# HDMI_DP.net
KiCad netlist of a schematic drawn in Altium Designer
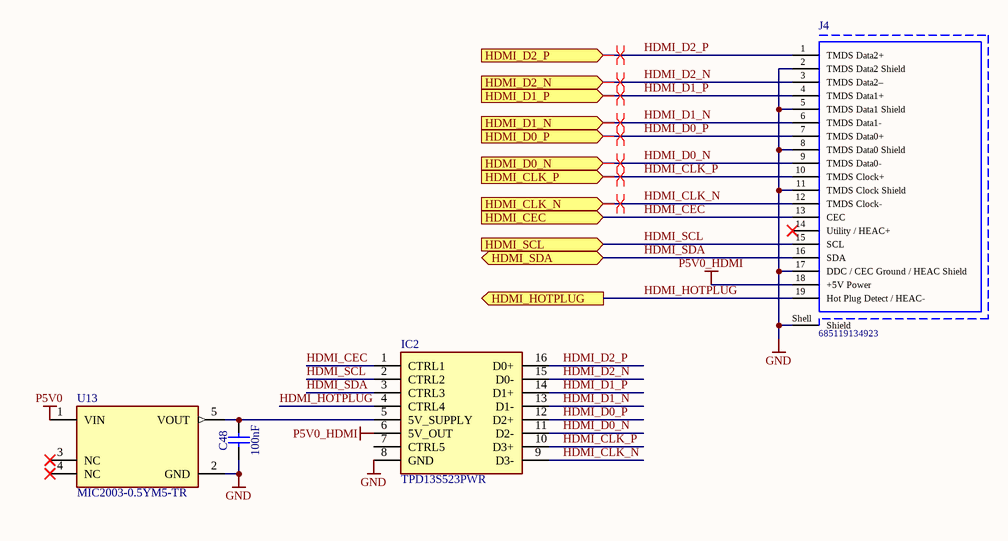
[diagram p0: HDMI_DP.SchDoc]

(export (version "E")
  (design (tool "Eeschema 10.0.6"))
  (components
    (comp (ref "C48")
      (value "100nF")
      (footprint "CAPC1005X55N")
      (description "Non-polarised capacitor")
      (fields
        (field (name "MANUFACTURER PART NUMBER") "CC0402_100NF_16V_10%_X5R")
        (field (name "MANUFACTURER") "GENERIC")
        (field (name "AUTHOR") "CERN DEM JLC")
      )
      (libsource (lib "Capacitors") (part "Capacitor - non polarized"))
    )
    (comp (ref "IC2")
      (value "TPD13S523PWR")
      (footprint "SamacSys:SOP65P640X120-16N")
      (description "Integrated Circuit")
      (libsource (lib "*") (part "TPD13S523PWR"))
    )
    (comp (ref "J4")
      (value "685119134923")
      (footprint "685119134923")
      (description "HDMI Type A Receptacle WR-HDMI, Horizontal, SMT")
      (fields (field (name "MANUFACTURER") "Wurth Elektronik") (field (name "PUBLISHER") "WurthElektronik"))
      (libsource (lib "Altium Content Vault") (part "WE-CN-1P-1F-HD19"))
    )
    (comp (ref "U13")
      (value "MIC2003-0.5YM5-TR")
      (footprint "FP-SOT23-5LD-PL-1-IPC_A")
      (description "IC PWR SWITCH P-CHAN 1:1 SOT23-5")
      (libsource (lib "Altium Content Vault") (part "469536bcd6fb6047f0a4e6547b251e2"))
    )
  )
  (nets
    (net (code "1") (name "/HDMI_CEC") (class "Default")
      (node (ref "IC2") (pin "1") (pinfunction "CTRL1_1") (pintype "passive"))
      (node (ref "J4") (pin "13") (pinfunction "CEC_13") (pintype "passive"))
    )
    (net (code "2") (name "/HDMI_CLK_N") (class "Default")
      (node (ref "IC2") (pin "9") (pinfunction "D3-_9") (pintype "passive"))
      (node (ref "J4") (pin "12") (pinfunction "TMDS_Clock-_12") (pintype "passive"))
    )
    (net (code "3") (name "/HDMI_CLK_P") (class "Default")
      (node (ref "IC2") (pin "10") (pinfunction "D3+_10") (pintype "passive"))
      (node (ref "J4") (pin "10") (pinfunction "TMDS_Clock+_10") (pintype "passive"))
    )
    (net (code "4") (name "/HDMI_D0_N") (class "Default")
      (node (ref "IC2") (pin "11") (pinfunction "D2-_11") (pintype "passive"))
      (node (ref "J4") (pin "9") (pinfunction "TMDS_Data0-_9") (pintype "passive"))
    )
    (net (code "5") (name "/HDMI_D0_P") (class "Default")
      (node (ref "IC2") (pin "12") (pinfunction "D2+_12") (pintype "passive"))
      (node (ref "J4") (pin "7") (pinfunction "TMDS_Data0+_7") (pintype "passive"))
    )
    (net (code "6") (name "/HDMI_D1_N") (class "Default")
      (node (ref "IC2") (pin "13") (pinfunction "D1-_13") (pintype "passive"))
      (node (ref "J4") (pin "6") (pinfunction "TMDS_Data1-_6") (pintype "passive"))
    )
    (net (code "7") (name "/HDMI_D1_P") (class "Default")
      (node (ref "IC2") (pin "14") (pinfunction "D1+_14") (pintype "passive"))
      (node (ref "J4") (pin "4") (pinfunction "TMDS_Data1+_4") (pintype "passive"))
    )
    (net (code "8") (name "/HDMI_D2_N") (class "Default")
      (node (ref "IC2") (pin "15") (pinfunction "D0-_15") (pintype "passive"))
      (node (ref "J4") (pin "3") (pinfunction "TMDS_Data2–_3") (pintype "passive"))
    )
    (net (code "9") (name "/HDMI_D2_P") (class "Default")
      (node (ref "IC2") (pin "16") (pinfunction "D0+_16") (pintype "passive"))
      (node (ref "J4") (pin "1") (pinfunction "TMDS_Data2+_1") (pintype "passive"))
    )
    (net (code "10") (name "/HDMI_HOTPLUG") (class "Default")
      (node (ref "IC2") (pin "4") (pinfunction "CTRL4_4") (pintype "passive"))
      (node (ref "J4") (pin "19") (pinfunction "Hot_Plug_Detect_/_HEAC-_19") (pintype "passive"))
    )
    (net (code "11") (name "/HDMI_SCL") (class "Default")
      (node (ref "IC2") (pin "2") (pinfunction "CTRL2_2") (pintype "passive"))
      (node (ref "J4") (pin "15") (pinfunction "SCL_15") (pintype "passive"))
    )
    (net (code "12") (name "/HDMI_SDA") (class "Default")
      (node (ref "IC2") (pin "3") (pinfunction "CTRL3_3") (pintype "passive"))
      (node (ref "J4") (pin "16") (pinfunction "SDA_16") (pintype "passive"))
    )
    (net (code "13") (name "GND") (class "Default")
      (node (ref "C48") (pin "1") (pinfunction "1_1") (pintype "passive"))
      (node (ref "IC2") (pin "8") (pinfunction "GND_8") (pintype "passive"))
      (node (ref "J4") (pin "11") (pinfunction "TMDS_Clock_Shield_11") (pintype "passive"))
      (node (ref "J4") (pin "17") (pinfunction "DDC_/_CEC_Ground_/_HEAC_Shield_17") (pintype "passive"))
      (node (ref "J4") (pin "2") (pinfunction "TMDS_Data2_Shield_2") (pintype "passive"))
      (node (ref "J4") (pin "5") (pinfunction "TMDS_Data1_Shield_5") (pintype "passive"))
      (node (ref "J4") (pin "8") (pinfunction "TMDS_Data0_Shield_8") (pintype "passive"))
      (node (ref "J4") (pin "Shell") (pinfunction "Shield_Shell") (pintype "passive"))
      (node (ref "U13") (pin "2") (pinfunction "GND_2") (pintype "power_in"))
    )
    (net (code "14") (name "Net-(IC2-5V_SUPPLY)") (class "Default")
      (node (ref "C48") (pin "2") (pinfunction "2_2") (pintype "passive"))
      (node (ref "IC2") (pin "5") (pinfunction "5V_SUPPLY_5") (pintype "passive"))
      (node (ref "U13") (pin "5") (pinfunction "VOUT_5") (pintype "output"))
    )
    (net (code "15") (name "P5V0") (class "Default")
      (node (ref "U13") (pin "1") (pinfunction "VIN_1") (pintype "power_in"))
    )
    (net (code "16") (name "P5V0_HDMI") (class "Default")
      (node (ref "IC2") (pin "6") (pinfunction "5V_OUT_6") (pintype "passive"))
      (node (ref "J4") (pin "18") (pinfunction "+5V_Power_18") (pintype "passive"))
    )
    (net (code "17") (name "unconnected-(IC2-CTRL5-Pad7)") (class "Default")
      (node (ref "IC2") (pin "7") (pinfunction "CTRL5_7") (pintype "passive"))
    )
    (net (code "18") (name "unconnected-(J4-Utility_{slash}_HEAC+-Pad14)") (class "Default")
      (node (ref "J4") (pin "14") (pinfunction "Utility_/_HEAC+_14") (pintype "passive+no_connect"))
    )
    (net (code "19") (name "unconnected-(U13-NC-Pad3)") (class "Default")
      (node (ref "U13") (pin "3") (pinfunction "NC_3") (pintype "passive+no_connect"))
    )
    (net (code "20") (name "unconnected-(U13-NC-Pad4)") (class "Default")
      (node (ref "U13") (pin "4") (pinfunction "NC_4") (pintype "passive+no_connect"))
    )
  )
)
